# TinyNES_RGB_Board.net
KiCad netlist of a schematic drawn in EAGLE
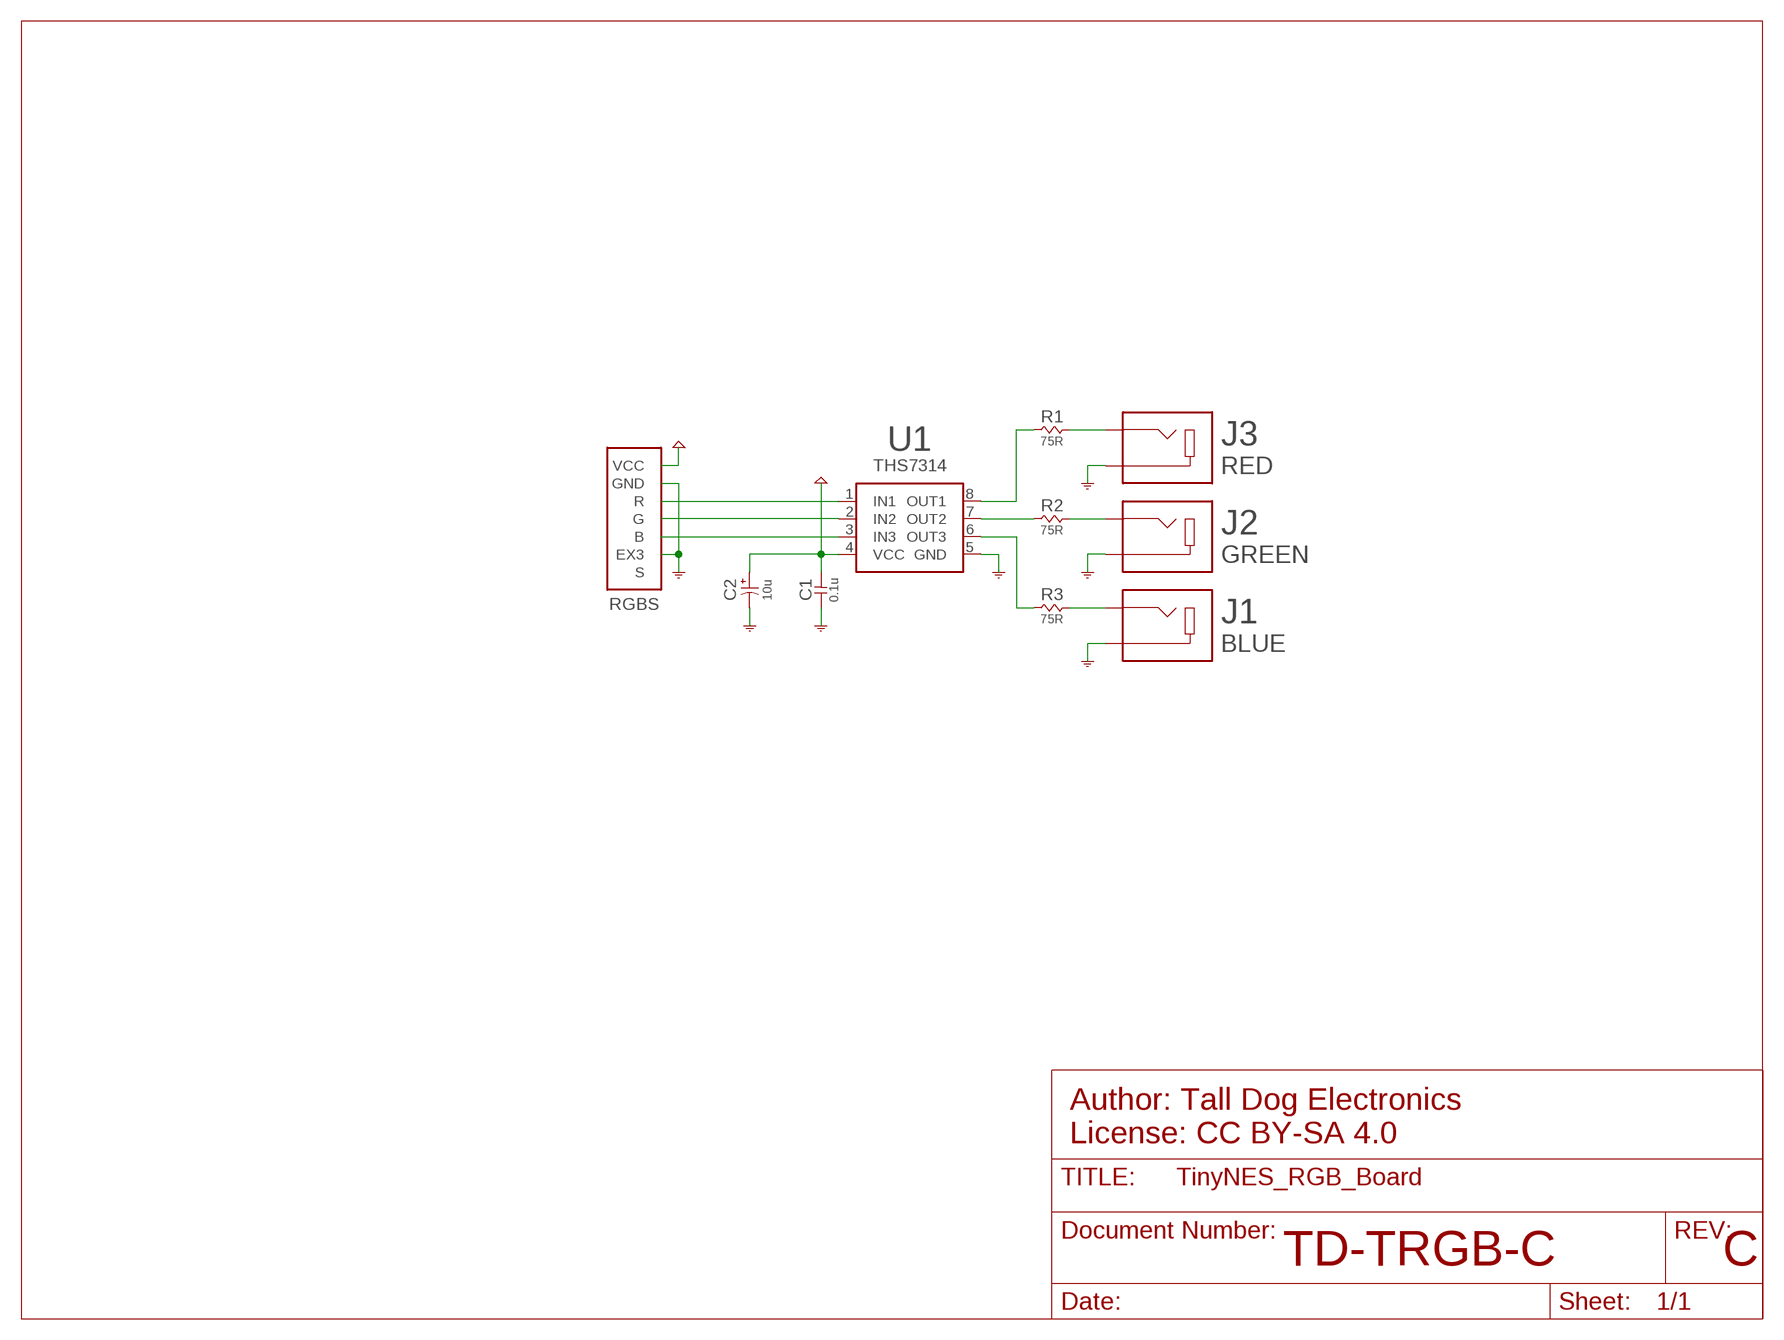
[diagram p0: schematic, sheet 1]

(export (version "E")
  (design (tool "Eeschema 10.0.6"))
  (components
    (comp (ref "C1")
      (value "0.1u")
      (footprint "eagle-import:0805-NP")
      (libsource (lib "eagle-import") (part "CAP-NP-0805"))
    )
    (comp (ref "C2")
      (value "10u")
      (footprint "eagle-import:1206-P")
      (libsource (lib "eagle-import") (part "CAP-P-1206"))
    )
    (comp (ref "J1")
      (value "BLUE")
      (footprint "eagle-import:RCJ-VERT")
      (libsource (lib "eagle-import") (part "JACK-VERT"))
    )
    (comp (ref "J2")
      (value "GREEN")
      (footprint "eagle-import:RCJ-VERT")
      (libsource (lib "eagle-import") (part "JACK-VERT"))
    )
    (comp (ref "J3")
      (value "RED")
      (footprint "eagle-import:RCJ-VERT")
      (libsource (lib "eagle-import") (part "JACK-VERT"))
    )
    (comp (ref "R1")
      (value "75R")
      (footprint "eagle-import:0805-NP")
      (libsource (lib "eagle-import") (part "RESISTOR-0805"))
    )
    (comp (ref "R2")
      (value "75R")
      (footprint "eagle-import:0805-NP")
      (libsource (lib "eagle-import") (part "RESISTOR-0805"))
    )
    (comp (ref "R3")
      (value "75R")
      (footprint "eagle-import:0805-NP")
      (libsource (lib "eagle-import") (part "RESISTOR-0805"))
    )
    (comp (ref "RGBS")
      (value "RGB-BOT")
      (footprint "eagle-import:RGB-BOT")
      (libsource (lib "eagle-import") (part "RGB-BOT"))
    )
    (comp (ref "U1")
      (value "THS7314")
      (footprint "eagle-import:SOIC-8")
      (libsource (lib "eagle-import") (part "THS7314"))
    )
  )
  (nets
    (net (code "1") (name "GND") (class "Default")
      (node (ref "C1") (pin "2") (pinfunction "2_2") (pintype "bidirectional"))
      (node (ref "C2") (pin "N") (pinfunction "C_N") (pintype "bidirectional"))
      (node (ref "J1") (pin "1") (pinfunction "S_1") (pintype "bidirectional"))
      (node (ref "J1") (pin "3") (pinfunction "S_3") (pintype "bidirectional"))
      (node (ref "J2") (pin "1") (pinfunction "S_1") (pintype "bidirectional"))
      (node (ref "J2") (pin "3") (pinfunction "S_3") (pintype "bidirectional"))
      (node (ref "J3") (pin "1") (pinfunction "S_1") (pintype "bidirectional"))
      (node (ref "J3") (pin "3") (pinfunction "S_3") (pintype "bidirectional"))
      (node (ref "RGBS") (pin "EXT3") (pinfunction "EX3_EXT3") (pintype "bidirectional"))
      (node (ref "RGBS") (pin "GND") (pinfunction "GND_GND") (pintype "bidirectional"))
      (node (ref "U1") (pin "5") (pinfunction "GND_5") (pintype "bidirectional"))
    )
    (net (code "2") (name "Net-(J1-T)") (class "Default")
      (node (ref "J1") (pin "2") (pinfunction "T_2") (pintype "bidirectional"))
      (node (ref "R3") (pin "2") (pinfunction "2_2") (pintype "bidirectional"))
    )
    (net (code "3") (name "Net-(J2-T)") (class "Default")
      (node (ref "J2") (pin "2") (pinfunction "T_2") (pintype "bidirectional"))
      (node (ref "R2") (pin "2") (pinfunction "2_2") (pintype "bidirectional"))
    )
    (net (code "4") (name "Net-(J3-T)") (class "Default")
      (node (ref "J3") (pin "2") (pinfunction "T_2") (pintype "bidirectional"))
      (node (ref "R1") (pin "2") (pinfunction "2_2") (pintype "bidirectional"))
    )
    (net (code "5") (name "Net-(U1-IN1)") (class "Default")
      (node (ref "RGBS") (pin "R") (pinfunction "R_R") (pintype "bidirectional"))
      (node (ref "U1") (pin "1") (pinfunction "IN1_1") (pintype "bidirectional"))
    )
    (net (code "6") (name "Net-(U1-IN2)") (class "Default")
      (node (ref "RGBS") (pin "G") (pinfunction "G_G") (pintype "bidirectional"))
      (node (ref "U1") (pin "2") (pinfunction "IN2_2") (pintype "bidirectional"))
    )
    (net (code "7") (name "Net-(U1-IN3)") (class "Default")
      (node (ref "RGBS") (pin "B") (pinfunction "B_B") (pintype "bidirectional"))
      (node (ref "U1") (pin "3") (pinfunction "IN3_3") (pintype "bidirectional"))
    )
    (net (code "8") (name "Net-(U1-OUT1)") (class "Default")
      (node (ref "R1") (pin "1") (pinfunction "1_1") (pintype "bidirectional"))
      (node (ref "U1") (pin "8") (pinfunction "OUT1_8") (pintype "bidirectional"))
    )
    (net (code "9") (name "Net-(U1-OUT2)") (class "Default")
      (node (ref "R2") (pin "1") (pinfunction "1_1") (pintype "bidirectional"))
      (node (ref "U1") (pin "7") (pinfunction "OUT2_7") (pintype "bidirectional"))
    )
    (net (code "10") (name "Net-(U1-OUT3)") (class "Default")
      (node (ref "R3") (pin "1") (pinfunction "1_1") (pintype "bidirectional"))
      (node (ref "U1") (pin "6") (pinfunction "OUT3_6") (pintype "bidirectional"))
    )
    (net (code "11") (name "VCC") (class "Default")
      (node (ref "C1") (pin "1") (pinfunction "1_1") (pintype "bidirectional"))
      (node (ref "C2") (pin "P") (pinfunction "A_P") (pintype "bidirectional"))
      (node (ref "RGBS") (pin "VCC@1") (pinfunction "VCC_VCC@1") (pintype "bidirectional"))
      (node (ref "RGBS") (pin "VCC@2") (pinfunction "VCC_VCC@2") (pintype "bidirectional"))
      (node (ref "RGBS") (pin "VCC@3") (pinfunction "VCC_VCC@3") (pintype "bidirectional"))
      (node (ref "U1") (pin "4") (pinfunction "VCC_4") (pintype "bidirectional"))
    )
    (net (code "12") (name "unconnected-(RGBS-PadS)") (class "Default")
      (node (ref "RGBS") (pin "S") (pinfunction "S_S") (pintype "bidirectional"))
    )
  )
)
